# 01-PLAN-B.net
KiCad netlist of a schematic drawn in Altium Designer
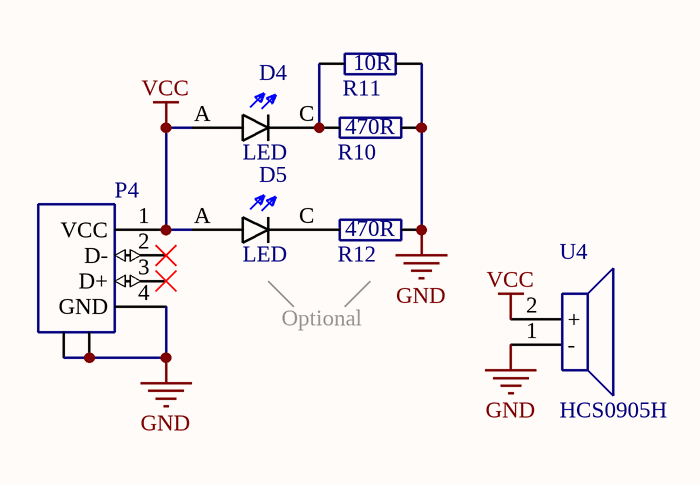
[diagram p0: 01-PLAN-B.SchDoc]

(export (version "E")
  (design (tool "Eeschema 10.0.6"))
  (components
    (comp (ref "D4")
      (value "LED")
      (footprint "LED_0805_INVERTED")
      (description "Led General")
      (fields (field (name "MF") "Dialight") (field (name "MP") "598-8140-107F"))
      (libsource (lib "ComponentsLib") (part "LED"))
    )
    (comp (ref "D5")
      (value "LED")
      (footprint "LED_0805_INVERTED")
      (description "Led General")
      (fields (field (name "MF") "Dialight") (field (name "MP") "598-8140-107F"))
      (libsource (lib "ComponentsLib") (part "LED"))
    )
    (comp (ref "P4")
      (value "440247-2")
      (footprint "USB A type r/a male DIP")
      (description "Mini/Micro USB B Type RCPT")
      (libsource (lib "ComponentsLib") (part "CON-USB-A"))
    )
    (comp (ref "R10")
      (value "~")
      (footprint "R0603_NOSILK")
      (description "Resistor General")
      (fields (field (name "TOLERANCE") "5%") (field (name "RESISTANCE") "470R"))
      (libsource (lib "A.Shelestov_Resistors") (part "R0603_470R"))
    )
    (comp (ref "R11")
      (value "~")
      (footprint "R0603_NOSILK")
      (description "Resistor General")
      (fields (field (name "TOLERANCE") "5%") (field (name "RESISTANCE") "10R"))
      (libsource (lib "A.Shelestov_Resistors") (part "R0603_10R"))
    )
    (comp (ref "R12")
      (value "~")
      (footprint "R0603_NOSILK")
      (description "Resistor General")
      (fields (field (name "TOLERANCE") "5%") (field (name "RESISTANCE") "470R"))
      (libsource (lib "A.Shelestov_Resistors") (part "R0603_470R"))
    )
    (comp (ref "U4")
      (value "HCS0905H")
      (footprint "HCS09H_THROUGH_HOLE")
      (description "5V Buzzer GEN")
      (libsource (lib "ComponentsLib") (part "HCS0905H"))
    )
  )
  (nets
    (net (code "1") (name "GND") (class "Default")
      (node (ref "P4") (pin "4") (pinfunction "GND_4") (pintype "passive"))
      (node (ref "P4") (pin "SHIELD") (pinfunction "SHIELD_SHIELD") (pintype "power_in"))
      (node (ref "R10") (pin "2") (pinfunction "2_2") (pintype "passive"))
      (node (ref "R11") (pin "2") (pinfunction "2_2") (pintype "passive"))
      (node (ref "R12") (pin "2") (pinfunction "2_2") (pintype "passive"))
      (node (ref "U4") (pin "1") (pinfunction "-_1") (pintype "passive"))
    )
    (net (code "2") (name "Net-(D4-PadC)") (class "Default")
      (node (ref "D4") (pin "C") (pinfunction "C_C") (pintype "passive"))
      (node (ref "R10") (pin "1") (pinfunction "1_1") (pintype "passive"))
      (node (ref "R11") (pin "1") (pinfunction "1_1") (pintype "passive"))
    )
    (net (code "3") (name "Net-(D5-PadC)") (class "Default")
      (node (ref "D5") (pin "C") (pinfunction "C_C") (pintype "passive"))
      (node (ref "R12") (pin "1") (pinfunction "1_1") (pintype "passive"))
    )
    (net (code "4") (name "VCC") (class "Default")
      (node (ref "D4") (pin "A") (pinfunction "A_A") (pintype "passive"))
      (node (ref "D5") (pin "A") (pinfunction "A_A") (pintype "passive"))
      (node (ref "P4") (pin "1") (pinfunction "VCC_1") (pintype "power_in"))
      (node (ref "U4") (pin "2") (pinfunction "+_2") (pintype "passive"))
    )
    (net (code "5") (name "unconnected-(P4-D+-Pad3)") (class "Default")
      (node (ref "P4") (pin "3") (pinfunction "D+_3") (pintype "bidirectional+no_connect"))
    )
    (net (code "6") (name "unconnected-(P4-D--Pad2)") (class "Default")
      (node (ref "P4") (pin "2") (pinfunction "D-_2") (pintype "bidirectional+no_connect"))
    )
  )
)
